# TindikSapi_V1_rev.net
KiCad netlist of a schematic drawn in EAGLE
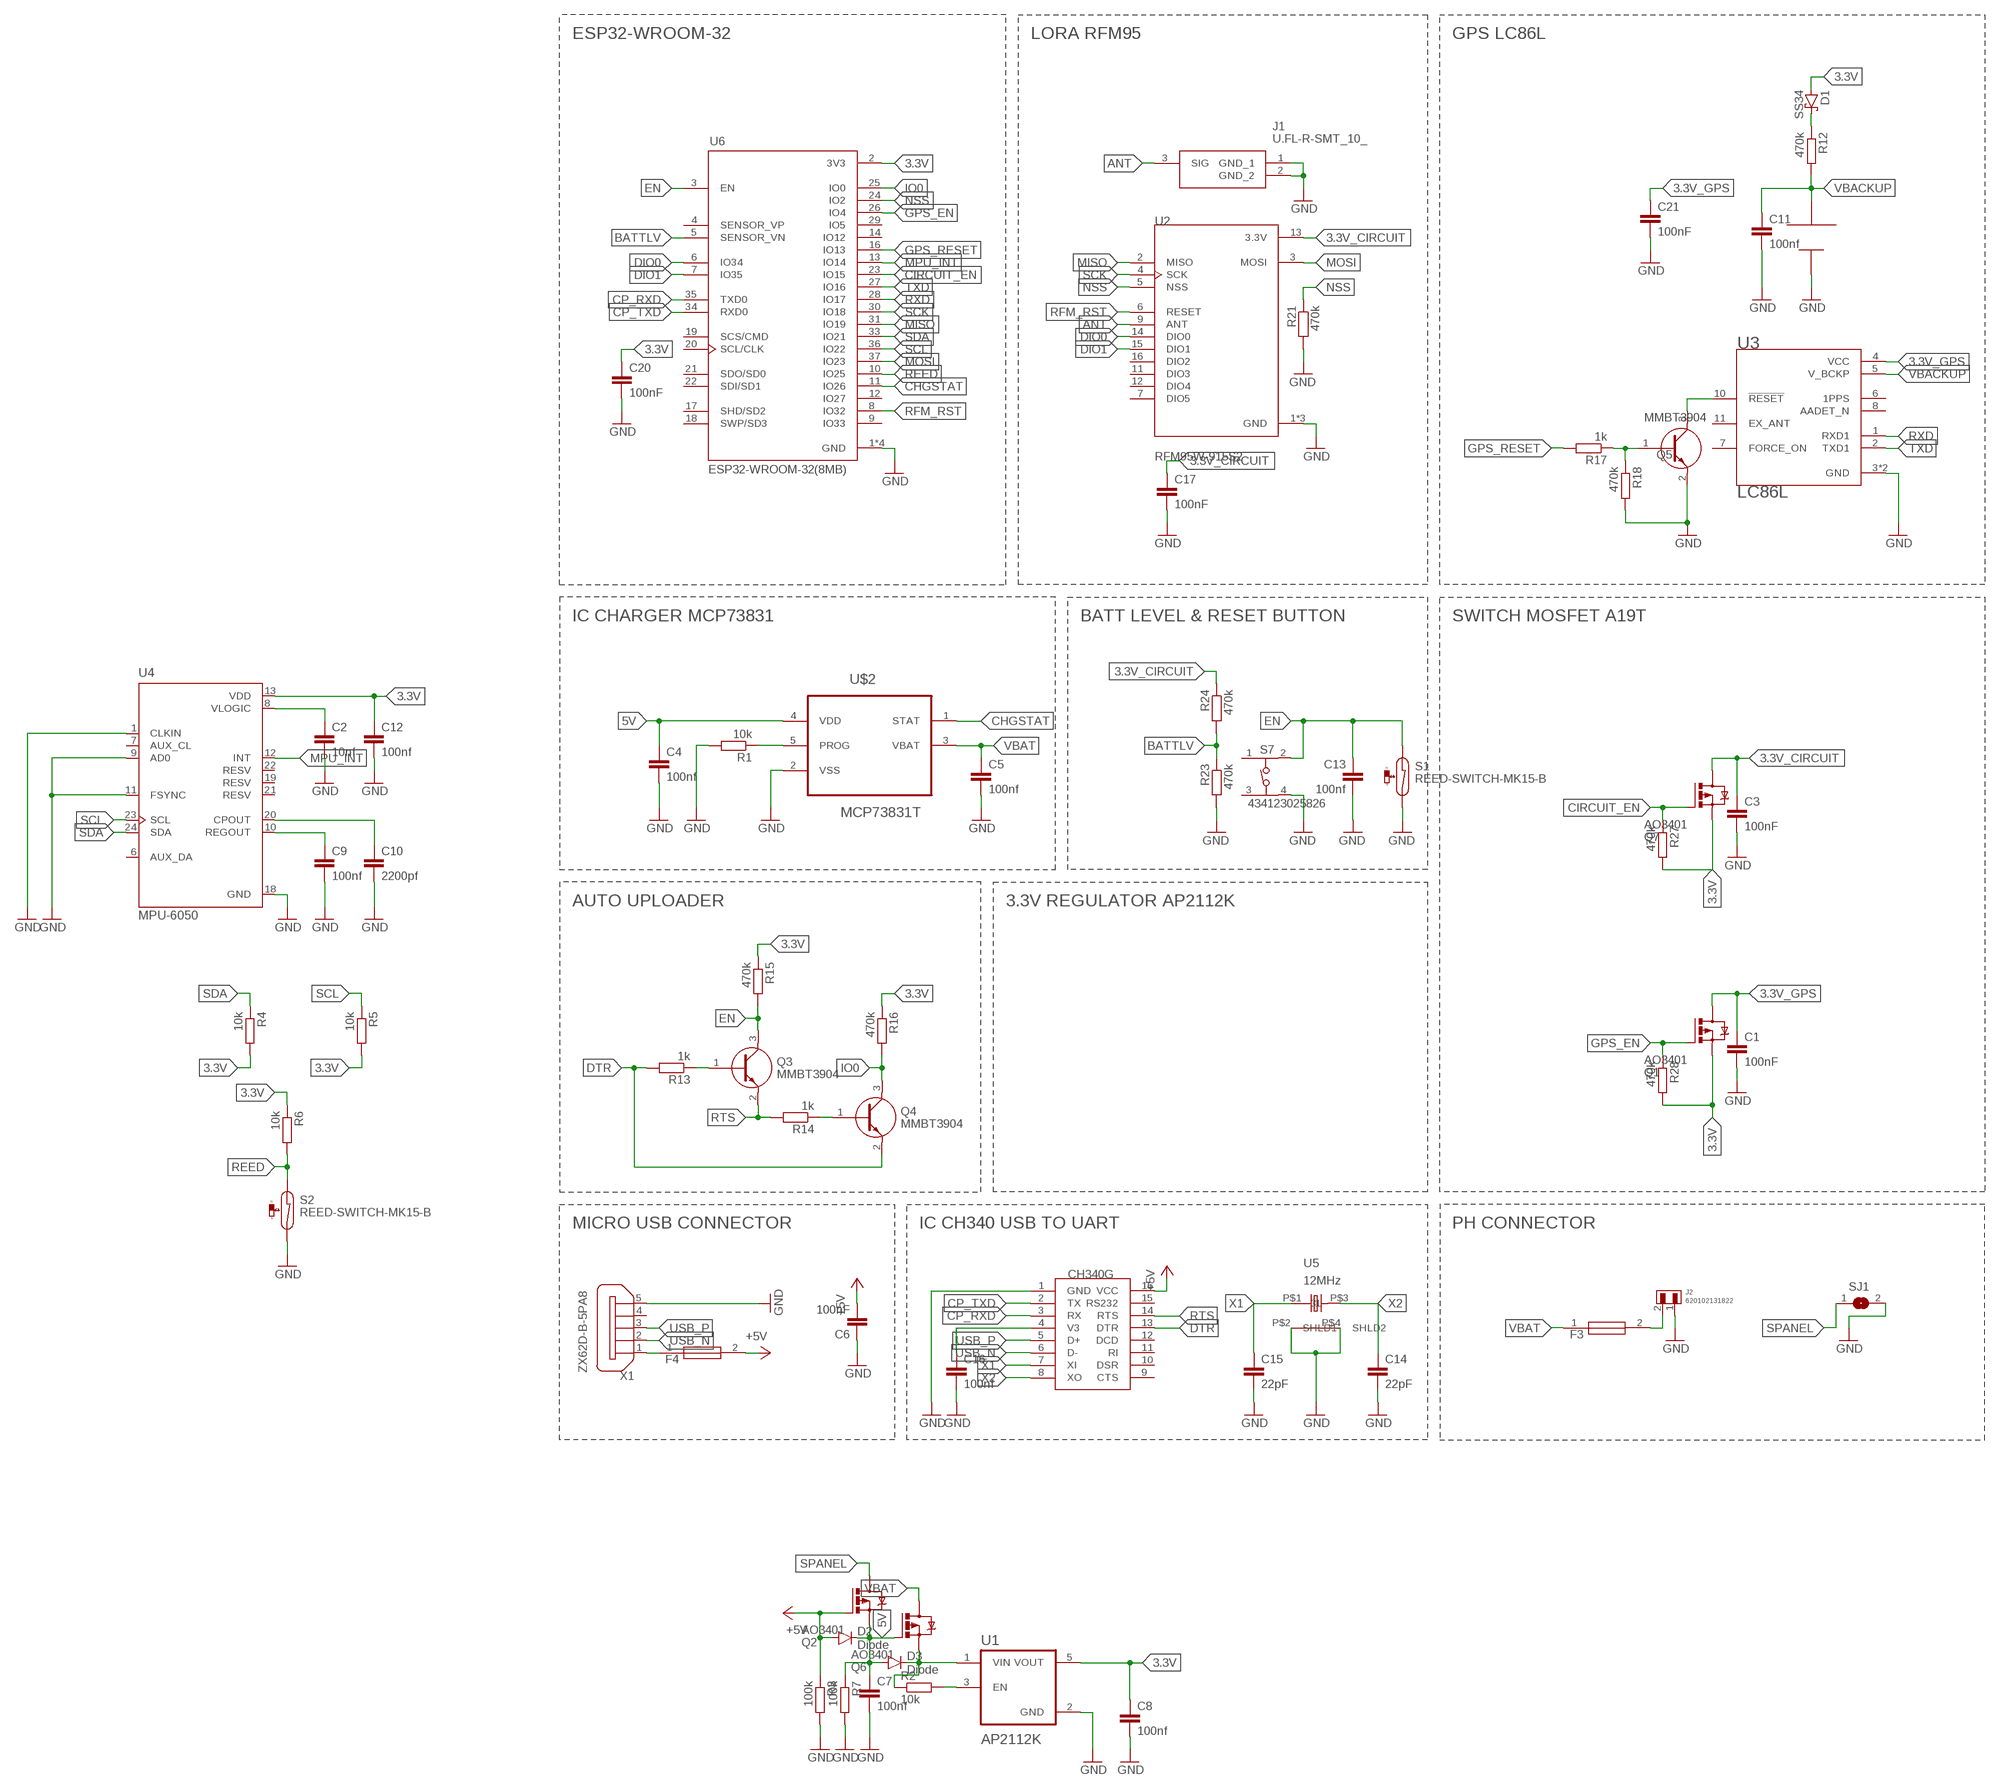
[diagram p0: schematic, sheet 1]

(export (version "E")
  (design (tool "Eeschema 10.0.6"))
  (components
    (comp (ref "C1")
      (value "100nF")
      (footprint "eagle-import:C0603")
      (libsource (lib "eagle-import") (part "C-EUC0603"))
    )
    (comp (ref "C2")
      (value "10nf")
      (footprint "eagle-import:C0603")
      (libsource (lib "eagle-import") (part "C-EUC0603"))
    )
    (comp (ref "C3")
      (value "100nF")
      (footprint "eagle-import:C0603")
      (libsource (lib "eagle-import") (part "C-EUC0603"))
    )
    (comp (ref "C4")
      (value "100nf")
      (footprint "eagle-import:C0603")
      (libsource (lib "eagle-import") (part "C-EUC0603"))
    )
    (comp (ref "C5")
      (value "100nf")
      (footprint "eagle-import:C0603")
      (libsource (lib "eagle-import") (part "C-EUC0603"))
    )
    (comp (ref "C6")
      (value "100nF")
      (footprint "eagle-import:C0603")
      (libsource (lib "eagle-import") (part "C-EUC0603"))
    )
    (comp (ref "C7")
      (value "100nf")
      (footprint "eagle-import:C0603")
      (libsource (lib "eagle-import") (part "C-EUC0603"))
    )
    (comp (ref "C8")
      (value "100nf")
      (footprint "eagle-import:C0603")
      (libsource (lib "eagle-import") (part "C-EUC0603"))
    )
    (comp (ref "C9")
      (value "100nf")
      (footprint "eagle-import:C0603")
      (libsource (lib "eagle-import") (part "C-EUC0603"))
    )
    (comp (ref "C10")
      (value "2200pf")
      (footprint "eagle-import:C0603")
      (libsource (lib "eagle-import") (part "C-EUC0603"))
    )
    (comp (ref "C11")
      (value "100nf")
      (footprint "eagle-import:C0603")
      (libsource (lib "eagle-import") (part "C-EUC0603"))
    )
    (comp (ref "C12")
      (value "100nf")
      (footprint "eagle-import:C0603")
      (libsource (lib "eagle-import") (part "C-EUC0603"))
    )
    (comp (ref "C13")
      (value "100nf")
      (footprint "eagle-import:C0603")
      (libsource (lib "eagle-import") (part "C-EUC0603"))
    )
    (comp (ref "C14")
      (value "22pF")
      (footprint "eagle-import:C0603")
      (libsource (lib "eagle-import") (part "C-EUC0603"))
    )
    (comp (ref "C15")
      (value "22pF")
      (footprint "eagle-import:C0603")
      (libsource (lib "eagle-import") (part "C-EUC0603"))
    )
    (comp (ref "C16")
      (value "100nf")
      (footprint "eagle-import:C0603")
      (libsource (lib "eagle-import") (part "C-EUC0603"))
    )
    (comp (ref "C17")
      (value "100nF")
      (footprint "eagle-import:C0603")
      (libsource (lib "eagle-import") (part "C-EUC0603"))
    )
    (comp (ref "C20")
      (value "100nF")
      (footprint "eagle-import:C0603")
      (libsource (lib "eagle-import") (part "C-EUC0603"))
    )
    (comp (ref "C21")
      (value "100nF")
      (footprint "eagle-import:C0603")
      (libsource (lib "eagle-import") (part "C-EUC0603"))
    )
    (comp (ref "D1")
      (value "SS34")
      (footprint "eagle-import:SMA")
      (fields
        (field (name "DIGIKEY_PART_NUMBER") "SS12FSCT-ND")
        (field (name "MANUFACTURER") "ON Semiconductor")
        (field (name "MPN") "SS12")
        (field (name "CREATED_BY") "PCBLayout.com")
      )
      (libsource (lib "eagle-import") (part "SS12"))
    )
    (comp (ref "D2")
      (value "Diode")
      (footprint "eagle-import:SOD123")
      (libsource (lib "eagle-import") (part "DIODE-SOD123"))
    )
    (comp (ref "D3")
      (value "Diode")
      (footprint "eagle-import:SOD123")
      (libsource (lib "eagle-import") (part "DIODE-SOD123"))
    )
    (comp (ref "F3")
      (value "FUSE 1A")
      (footprint "eagle-import:FUSC3216X100N")
      (fields
        (field (name "ARROW_PART_NUMBER") "MF-NSML260/12-2")
        (field (name "MOUSER_PART_NUMBER") "652-MF-NSML260/12-2")
      )
      (libsource (lib "eagle-import") (part "MF-NSML260_12-2"))
    )
    (comp (ref "F4")
      (value "FUSE 1A")
      (footprint "eagle-import:FUSC3216X100N")
      (fields
        (field (name "ARROW_PART_NUMBER") "MF-NSML260/12-2")
        (field (name "MOUSER_PART_NUMBER") "652-MF-NSML260/12-2")
      )
      (libsource (lib "eagle-import") (part "MF-NSML260_12-2"))
    )
    (comp (ref "J1")
      (value "U.FL-R-SMT_10_")
      (footprint "eagle-import:UFLRSMT10")
      (fields
        (field (name "ARROW_PART_NUMBER") "U.FL-R-SMT(10)")
        (field (name "MOUSER_PART_NUMBER") "798-U.FL-R-SMT10")
      )
      (libsource (lib "eagle-import") (part "U.FL-R-SMT_10_"))
    )
    (comp (ref "J2")
      (value "620102131822")
      (footprint "eagle-import:620102131822")
      (libsource (lib "eagle-import") (part "620102131822"))
    )
    (comp (ref "Q1")
      (value "AO3401")
      (footprint "eagle-import:SOT23")
      (libsource (lib "eagle-import") (part "PMOSFETSOT23_"))
    )
    (comp (ref "Q2")
      (value "AO3401")
      (footprint "eagle-import:SOT23")
      (libsource (lib "eagle-import") (part "PMOSFETSOT23_"))
    )
    (comp (ref "Q3")
      (value "MMBT3904")
      (footprint "eagle-import:SOT95P240X120-3N")
      (fields (field (name "MOUSER_PART_NUMBER") "512-MMBT3904"))
      (libsource (lib "eagle-import") (part "MMBT3904"))
    )
    (comp (ref "Q4")
      (value "MMBT3904")
      (footprint "eagle-import:SOT95P240X120-3N")
      (fields (field (name "MOUSER_PART_NUMBER") "512-MMBT3904"))
      (libsource (lib "eagle-import") (part "MMBT3904"))
    )
    (comp (ref "Q5")
      (value "MMBT3904")
      (footprint "eagle-import:SOT95P240X120-3N")
      (fields (field (name "MOUSER_PART_NUMBER") "512-MMBT3904"))
      (libsource (lib "eagle-import") (part "MMBT3904"))
    )
    (comp (ref "Q6")
      (value "AO3401")
      (footprint "eagle-import:SOT23")
      (libsource (lib "eagle-import") (part "PMOSFETSOT23_"))
    )
    (comp (ref "Q7")
      (value "AO3401")
      (footprint "eagle-import:SOT23")
      (libsource (lib "eagle-import") (part "PMOSFETSOT23_"))
    )
    (comp (ref "R1")
      (value "10k")
      (footprint "eagle-import:R0603")
      (libsource (lib "eagle-import") (part "R-EU_R0603"))
    )
    (comp (ref "R2")
      (value "10k")
      (footprint "eagle-import:R0603")
      (libsource (lib "eagle-import") (part "R-EU_R0603"))
    )
    (comp (ref "R3")
      (value "100k")
      (footprint "eagle-import:R0603")
      (libsource (lib "eagle-import") (part "R-EU_R0603"))
    )
    (comp (ref "R4")
      (value "10k")
      (footprint "eagle-import:R0603")
      (libsource (lib "eagle-import") (part "R-EU_R0603"))
    )
    (comp (ref "R5")
      (value "10k")
      (footprint "eagle-import:R0603")
      (libsource (lib "eagle-import") (part "R-EU_R0603"))
    )
    (comp (ref "R6")
      (value "10k")
      (footprint "eagle-import:R0603")
      (libsource (lib "eagle-import") (part "R-EU_R0603"))
    )
    (comp (ref "R7")
      (value "100k")
      (footprint "eagle-import:R0603")
      (libsource (lib "eagle-import") (part "R-EU_R0603"))
    )
    (comp (ref "R12")
      (value "470k")
      (footprint "eagle-import:R0603")
      (libsource (lib "eagle-import") (part "R-EU_R0603"))
    )
    (comp (ref "R13")
      (value "1k")
      (footprint "eagle-import:R0603")
      (libsource (lib "eagle-import") (part "R-EU_R0603"))
    )
    (comp (ref "R14")
      (value "1k")
      (footprint "eagle-import:R0603")
      (libsource (lib "eagle-import") (part "R-EU_R0603"))
    )
    (comp (ref "R15")
      (value "470k")
      (footprint "eagle-import:R0603")
      (libsource (lib "eagle-import") (part "R-EU_R0603"))
    )
    (comp (ref "R16")
      (value "470k")
      (footprint "eagle-import:R0603")
      (libsource (lib "eagle-import") (part "R-EU_R0603"))
    )
    (comp (ref "R17")
      (value "1k")
      (footprint "eagle-import:R0603")
      (libsource (lib "eagle-import") (part "R-EU_R0603"))
    )
    (comp (ref "R18")
      (value "470k")
      (footprint "eagle-import:R0603")
      (libsource (lib "eagle-import") (part "R-EU_R0603"))
    )
    (comp (ref "R21")
      (value "470k")
      (footprint "eagle-import:R0603")
      (libsource (lib "eagle-import") (part "R-EU_R0603"))
    )
    (comp (ref "R23")
      (value "470k")
      (footprint "eagle-import:R0603")
      (libsource (lib "eagle-import") (part "R-EU_R0603"))
    )
    (comp (ref "R24")
      (value "470k")
      (footprint "eagle-import:R0603")
      (libsource (lib "eagle-import") (part "R-EU_R0603"))
    )
    (comp (ref "R27")
      (value "470k")
      (footprint "eagle-import:R0603")
      (libsource (lib "eagle-import") (part "R-EU_R0603"))
    )
    (comp (ref "R28")
      (value "470k")
      (footprint "eagle-import:R0603")
      (libsource (lib "eagle-import") (part "R-EU_R0603"))
    )
    (comp (ref "S1")
      (value "REED-SWITCH-MK15-B")
      (footprint "eagle-import:MK15")
      (fields (field (name "MF") "MEDER") (field (name "MPN") "MK15-B-2"))
      (libsource (lib "eagle-import") (part "REED-SWITCH-MK15-B"))
    )
    (comp (ref "S2")
      (value "REED-SWITCH-MK15-B")
      (footprint "eagle-import:MK15")
      (fields (field (name "MF") "MEDER") (field (name "MPN") "MK15-B-2"))
      (libsource (lib "eagle-import") (part "REED-SWITCH-MK15-B"))
    )
    (comp (ref "S7")
      (value "434123025826")
      (footprint "eagle-import:434123025826")
      (libsource (lib "eagle-import") (part "434123025826"))
    )
    (comp (ref "SJ1")
      (value "SJW")
      (footprint "eagle-import:SJW")
      (libsource (lib "eagle-import") (part "SJW"))
    )
    (comp (ref "U$2")
      (value "MCP73831T")
      (footprint "eagle-import:SOT95P280X145-5N")
      (fields (field (name "MF") "Microchip") (field (name "MP") "MCP73831T-5ACI/OT"))
      (libsource (lib "eagle-import") (part "MCP73831T-5ACI/OT"))
    )
    (comp (ref "U$3")
      (value "MS621FE")
      (footprint "eagle-import:MS621FE")
      (libsource (lib "eagle-import") (part "MS621FE"))
    )
    (comp (ref "U$5")
      (value "CH340G")
      (footprint "eagle-import:SOIC127P600X175-16N")
      (libsource (lib "eagle-import") (part "CH340G-3D"))
    )
    (comp (ref "U1")
      (value "AP2112K")
      (footprint "eagle-import:SOT95P285X140-5N")
      (fields (field (name "MF") "Diodes Inc.") (field (name "MP") "AP2112K-3.3TRG1"))
      (libsource (lib "eagle-import") (part "AP2112K-3.3TRG1"))
    )
    (comp (ref "U2")
      (value "RFM95W-915S2")
      (footprint "eagle-import:XCVR_RFM95W-915S2")
      (fields (field (name "MF") "RF Solutions"))
      (libsource (lib "eagle-import") (part "RFM95W-915S2"))
    )
    (comp (ref "U3")
      (value "LC86L")
      (footprint "eagle-import:XCVR_L86-M33")
      (fields (field (name "MF") "Quectel") (field (name "MP") "L86-M33"))
      (libsource (lib "eagle-import") (part "L86-M33"))
    )
    (comp (ref "U4")
      (value "MPU-6050")
      (footprint "eagle-import:QFN50P400X400X95-24N")
      (fields (field (name "MF") "TDK InvenSense"))
      (libsource (lib "eagle-import") (part "MPU-6050"))
    )
    (comp (ref "U5")
      (value "12MHz")
      (footprint "eagle-import:NX32256A")
      (fields (field (name "MF") "NDK America,") (field (name "MP") "NX3225SA"))
      (libsource (lib "eagle-import") (part "NX3225SA"))
    )
    (comp (ref "U6")
      (value "ESP32-WROOM-32(8MB)")
      (footprint "eagle-import:MODULE_ESP32-WROOM-32(8MB)")
      (fields (field (name "MF") "Espressif Systems") (field (name "MP") "ESP32-WROOM-32 (8MB)"))
      (libsource (lib "eagle-import") (part "ESP32-WROOM-32(8MB)"))
    )
    (comp (ref "X1")
      (value "ZX62D-B-5PA8")
      (footprint "eagle-import:ZX62D-B-5PA8")
      (fields (field (name "MF") "Hirose"))
      (libsource (lib "eagle-import") (part "ZX62D-B-5PA8"))
    )
  )
  (nets
    (net (code "1") (name "+5V") (class "Default")
      (node (ref "C6") (pin "2") (pinfunction "2_2") (pintype "passive"))
      (node (ref "D2") (pin "A") (pinfunction "A_A") (pintype "passive"))
      (node (ref "F4") (pin "2") (pinfunction "2_2") (pintype "bidirectional"))
      (node (ref "Q2") (pin "1") (pinfunction "G_1") (pintype "passive"))
      (node (ref "R3") (pin "1") (pinfunction "1_1") (pintype "passive"))
      (node (ref "U$5") (pin "16") (pinfunction "VCC_16") (pintype "bidirectional"))
    )
    (net (code "2") (name "3.3V") (class "Default")
      (node (ref "C12") (pin "1") (pinfunction "1_1") (pintype "passive"))
      (node (ref "C20") (pin "1") (pinfunction "1_1") (pintype "passive"))
      (node (ref "C8") (pin "1") (pinfunction "1_1") (pintype "passive"))
      (node (ref "D1") (pin "A") (pinfunction "A_A") (pintype "passive"))
      (node (ref "Q1") (pin "2") (pinfunction "S_2") (pintype "passive"))
      (node (ref "Q7") (pin "2") (pinfunction "S_2") (pintype "passive"))
      (node (ref "R15") (pin "1") (pinfunction "1_1") (pintype "passive"))
      (node (ref "R16") (pin "1") (pinfunction "1_1") (pintype "passive"))
      (node (ref "R27") (pin "2") (pinfunction "2_2") (pintype "passive"))
      (node (ref "R28") (pin "2") (pinfunction "2_2") (pintype "passive"))
      (node (ref "R4") (pin "2") (pinfunction "2_2") (pintype "passive"))
      (node (ref "R5") (pin "2") (pinfunction "2_2") (pintype "passive"))
      (node (ref "R6") (pin "1") (pinfunction "1_1") (pintype "passive"))
      (node (ref "U1") (pin "5") (pinfunction "VOUT_5") (pintype "power_in"))
      (node (ref "U4") (pin "13") (pinfunction "VDD_13") (pintype "power_in"))
      (node (ref "U6") (pin "2") (pinfunction "3V3_2") (pintype "power_in"))
    )
    (net (code "3") (name "3.3V_CIRCUIT") (class "Default")
      (node (ref "C17") (pin "1") (pinfunction "1_1") (pintype "passive"))
      (node (ref "C3") (pin "1") (pinfunction "1_1") (pintype "passive"))
      (node (ref "Q7") (pin "3") (pinfunction "D_3") (pintype "passive"))
      (node (ref "R24") (pin "1") (pinfunction "1_1") (pintype "passive"))
      (node (ref "U2") (pin "13") (pinfunction "3.3V_13") (pintype "power_in"))
    )
    (net (code "4") (name "3.3V_GPS") (class "Default")
      (node (ref "C1") (pin "1") (pinfunction "1_1") (pintype "passive"))
      (node (ref "C21") (pin "1") (pinfunction "1_1") (pintype "passive"))
      (node (ref "Q1") (pin "3") (pinfunction "D_3") (pintype "passive"))
      (node (ref "U3") (pin "4") (pinfunction "VCC_4") (pintype "power_in"))
    )
    (net (code "5") (name "5V") (class "Default")
      (node (ref "C4") (pin "1") (pinfunction "1_1") (pintype "passive"))
      (node (ref "C7") (pin "1") (pinfunction "1_1") (pintype "passive"))
      (node (ref "D2") (pin "C") (pinfunction "C_C") (pintype "passive"))
      (node (ref "D3") (pin "A") (pinfunction "A_A") (pintype "passive"))
      (node (ref "Q2") (pin "2") (pinfunction "S_2") (pintype "passive"))
      (node (ref "Q6") (pin "1") (pinfunction "G_1") (pintype "passive"))
      (node (ref "R7") (pin "1") (pinfunction "1_1") (pintype "passive"))
      (node (ref "U$2") (pin "4") (pinfunction "VDD_4") (pintype "power_in"))
    )
    (net (code "6") (name "ANT") (class "Default")
      (node (ref "J1") (pin "3") (pinfunction "SIG_3") (pintype "bidirectional"))
      (node (ref "U2") (pin "9") (pinfunction "ANT_9") (pintype "bidirectional"))
    )
    (net (code "7") (name "BATTLV") (class "Default")
      (node (ref "R23") (pin "1") (pinfunction "1_1") (pintype "passive"))
      (node (ref "R24") (pin "2") (pinfunction "2_2") (pintype "passive"))
      (node (ref "U6") (pin "5") (pinfunction "SENSOR_VN_5") (pintype "input"))
    )
    (net (code "8") (name "CHGSTAT") (class "Default")
      (node (ref "U$2") (pin "1") (pinfunction "STAT_1") (pintype "output"))
      (node (ref "U6") (pin "11") (pinfunction "IO26_11") (pintype "bidirectional"))
    )
    (net (code "9") (name "CIRCUIT_EN") (class "Default")
      (node (ref "Q7") (pin "1") (pinfunction "G_1") (pintype "passive"))
      (node (ref "R27") (pin "1") (pinfunction "1_1") (pintype "passive"))
      (node (ref "U6") (pin "23") (pinfunction "IO15_23") (pintype "bidirectional"))
    )
    (net (code "10") (name "CP_RXD") (class "Default")
      (node (ref "U$5") (pin "3") (pinfunction "RX_3") (pintype "bidirectional"))
      (node (ref "U6") (pin "35") (pinfunction "TXD0_35") (pintype "bidirectional"))
    )
    (net (code "11") (name "CP_TXD") (class "Default")
      (node (ref "U$5") (pin "2") (pinfunction "TX_2") (pintype "bidirectional"))
      (node (ref "U6") (pin "34") (pinfunction "RXD0_34") (pintype "bidirectional"))
    )
    (net (code "12") (name "DIO0") (class "Default")
      (node (ref "U2") (pin "14") (pinfunction "DIO0_14") (pintype "bidirectional"))
      (node (ref "U6") (pin "6") (pinfunction "IO34_6") (pintype "input"))
    )
    (net (code "13") (name "DIO1") (class "Default")
      (node (ref "U2") (pin "15") (pinfunction "DIO1_15") (pintype "bidirectional"))
      (node (ref "U6") (pin "7") (pinfunction "IO35_7") (pintype "input"))
    )
    (net (code "14") (name "DTR") (class "Default")
      (node (ref "Q4") (pin "2") (pinfunction "E_2") (pintype "bidirectional"))
      (node (ref "R13") (pin "2") (pinfunction "2_2") (pintype "passive"))
      (node (ref "U$5") (pin "13") (pinfunction "DTR_13") (pintype "bidirectional"))
    )
    (net (code "15") (name "EN") (class "Default")
      (node (ref "C13") (pin "1") (pinfunction "1_1") (pintype "passive"))
      (node (ref "Q3") (pin "3") (pinfunction "C_3") (pintype "bidirectional"))
      (node (ref "R15") (pin "2") (pinfunction "2_2") (pintype "passive"))
      (node (ref "S1") (pin "1") (pinfunction "1_1") (pintype "passive"))
      (node (ref "S7") (pin "2") (pinfunction "2_2") (pintype "passive"))
      (node (ref "U6") (pin "3") (pinfunction "EN_3") (pintype "input"))
    )
    (net (code "16") (name "GND") (class "Default")
      (node (ref "C1") (pin "2") (pinfunction "2_2") (pintype "passive"))
      (node (ref "C10") (pin "2") (pinfunction "2_2") (pintype "passive"))
      (node (ref "C11") (pin "2") (pinfunction "2_2") (pintype "passive"))
      (node (ref "C12") (pin "2") (pinfunction "2_2") (pintype "passive"))
      (node (ref "C13") (pin "2") (pinfunction "2_2") (pintype "passive"))
      (node (ref "C14") (pin "2") (pinfunction "2_2") (pintype "passive"))
      (node (ref "C15") (pin "2") (pinfunction "2_2") (pintype "passive"))
      (node (ref "C16") (pin "2") (pinfunction "2_2") (pintype "passive"))
      (node (ref "C17") (pin "2") (pinfunction "2_2") (pintype "passive"))
      (node (ref "C2") (pin "2") (pinfunction "2_2") (pintype "passive"))
      (node (ref "C20") (pin "2") (pinfunction "2_2") (pintype "passive"))
      (node (ref "C21") (pin "2") (pinfunction "2_2") (pintype "passive"))
      (node (ref "C3") (pin "2") (pinfunction "2_2") (pintype "passive"))
      (node (ref "C4") (pin "2") (pinfunction "2_2") (pintype "passive"))
      (node (ref "C5") (pin "2") (pinfunction "2_2") (pintype "passive"))
      (node (ref "C6") (pin "1") (pinfunction "1_1") (pintype "passive"))
      (node (ref "C7") (pin "2") (pinfunction "2_2") (pintype "passive"))
      (node (ref "C8") (pin "2") (pinfunction "2_2") (pintype "passive"))
      (node (ref "C9") (pin "2") (pinfunction "2_2") (pintype "passive"))
      (node (ref "J1") (pin "1") (pinfunction "GND_1_1") (pintype "bidirectional"))
      (node (ref "J1") (pin "2") (pinfunction "GND_2_2") (pintype "bidirectional"))
      (node (ref "J2") (pin "1") (pinfunction "1_1") (pintype "passive"))
      (node (ref "Q5") (pin "2") (pinfunction "E_2") (pintype "bidirectional"))
      (node (ref "R1") (pin "2") (pinfunction "2_2") (pintype "passive"))
      (node (ref "R18") (pin "2") (pinfunction "2_2") (pintype "passive"))
      (node (ref "R21") (pin "2") (pinfunction "2_2") (pintype "passive"))
      (node (ref "R23") (pin "2") (pinfunction "2_2") (pintype "passive"))
      (node (ref "R3") (pin "2") (pinfunction "2_2") (pintype "passive"))
      (node (ref "R7") (pin "2") (pinfunction "2_2") (pintype "passive"))
      (node (ref "S1") (pin "2") (pinfunction "2_2") (pintype "passive"))
      (node (ref "S2") (pin "2") (pinfunction "2_2") (pintype "passive"))
      (node (ref "S7") (pin "4") (pinfunction "4_4") (pintype "passive"))
      (node (ref "SJ1") (pin "2") (pinfunction "2_2") (pintype "passive"))
      (node (ref "U$2") (pin "2") (pinfunction "VSS_2") (pintype "power_in"))
      (node (ref "U$3") (pin "V-") (pinfunction "V-_V-") (pintype "bidirectional"))
      (node (ref "U$5") (pin "1") (pinfunction "GND_1") (pintype "bidirectional"))
      (node (ref "U1") (pin "2") (pinfunction "GND_2") (pintype "power_in"))
      (node (ref "U2") (pin "1") (pinfunction "GND_1") (pintype "power_in"))
      (node (ref "U2") (pin "10") (pinfunction "GND_10") (pintype "power_in"))
      (node (ref "U2") (pin "8") (pinfunction "GND_8") (pintype "power_in"))
      (node (ref "U3") (pin "12") (pinfunction "GND_12") (pintype "passive"))
      (node (ref "U3") (pin "3") (pinfunction "GND_3") (pintype "passive"))
      (node (ref "U4") (pin "1") (pinfunction "CLKIN_1") (pintype "input"))
      (node (ref "U4") (pin "11") (pinfunction "FSYNC_11") (pintype "input"))
      (node (ref "U4") (pin "18") (pinfunction "GND_18") (pintype "power_in"))
      (node (ref "U4") (pin "9") (pinfunction "AD0_9") (pintype "input"))
      (node (ref "U5") (pin "P$2") (pinfunction "SHLD1_P$2") (pintype "passive"))
      (node (ref "U5") (pin "P$4") (pinfunction "SHLD2_P$4") (pintype "passive"))
      (node (ref "U6") (pin "1") (pinfunction "GND_1") (pintype "power_in"))
      (node (ref "U6") (pin "15") (pinfunction "GND_15") (pintype "power_in"))
      (node (ref "U6") (pin "38") (pinfunction "GND_38") (pintype "power_in"))
      (node (ref "U6") (pin "39") (pinfunction "GND_39") (pintype "power_in"))
      (node (ref "X1") (pin "5") (pinfunction "5_5") (pintype "passive"))
    )
    (net (code "17") (name "GPS_EN") (class "Default")
      (node (ref "Q1") (pin "1") (pinfunction "G_1") (pintype "passive"))
      (node (ref "R28") (pin "1") (pinfunction "1_1") (pintype "passive"))
      (node (ref "U6") (pin "26") (pinfunction "IO4_26") (pintype "bidirectional"))
    )
    (net (code "18") (name "GPS_RESET") (class "Default")
      (node (ref "R17") (pin "2") (pinfunction "2_2") (pintype "passive"))
      (node (ref "U6") (pin "16") (pinfunction "IO13_16") (pintype "bidirectional"))
    )
    (net (code "19") (name "IO0") (class "Default")
      (node (ref "Q4") (pin "3") (pinfunction "C_3") (pintype "bidirectional"))
      (node (ref "R16") (pin "2") (pinfunction "2_2") (pintype "passive"))
      (node (ref "U6") (pin "25") (pinfunction "IO0_25") (pintype "bidirectional"))
    )
    (net (code "20") (name "MISO") (class "Default")
      (node (ref "U2") (pin "2") (pinfunction "MISO_2") (pintype "input"))
      (node (ref "U6") (pin "31") (pinfunction "IO19_31") (pintype "bidirectional"))
    )
    (net (code "21") (name "MOSI") (class "Default")
      (node (ref "U2") (pin "3") (pinfunction "MOSI_3") (pintype "output"))
      (node (ref "U6") (pin "37") (pinfunction "IO23_37") (pintype "bidirectional"))
    )
    (net (code "22") (name "MPU_INT") (class "Default")
      (node (ref "U4") (pin "12") (pinfunction "INT_12") (pintype "output"))
      (node (ref "U6") (pin "13") (pinfunction "IO14_13") (pintype "bidirectional"))
    )
    (net (code "23") (name "NSS") (class "Default")
      (node (ref "R21") (pin "1") (pinfunction "1_1") (pintype "passive"))
      (node (ref "U2") (pin "5") (pinfunction "NSS_5") (pintype "input"))
      (node (ref "U6") (pin "24") (pinfunction "IO2_24") (pintype "bidirectional"))
    )
    (net (code "24") (name "Net-(D1-PadC)") (class "Default")
      (node (ref "D1") (pin "C") (pinfunction "C_C") (pintype "passive"))
      (node (ref "R12") (pin "1") (pinfunction "1_1") (pintype "passive"))
    )
    (net (code "25") (name "Net-(F3-Pad2)") (class "Default")
      (node (ref "F3") (pin "2") (pinfunction "2_2") (pintype "bidirectional"))
      (node (ref "J2") (pin "2") (pinfunction "2_2") (pintype "passive"))
    )
    (net (code "26") (name "Net-(F4-Pad1)") (class "Default")
      (node (ref "F4") (pin "1") (pinfunction "1_1") (pintype "bidirectional"))
      (node (ref "X1") (pin "1") (pinfunction "1_1") (pintype "passive"))
    )
    (net (code "27") (name "Net-(Q3-B)") (class "Default")
      (node (ref "Q3") (pin "1") (pinfunction "B_1") (pintype "bidirectional"))
      (node (ref "R13") (pin "1") (pinfunction "1_1") (pintype "passive"))
    )
    (net (code "28") (name "Net-(Q4-B)") (class "Default")
      (node (ref "Q4") (pin "1") (pinfunction "B_1") (pintype "bidirectional"))
      (node (ref "R14") (pin "1") (pinfunction "1_1") (pintype "passive"))
    )
    (net (code "29") (name "Net-(Q5-B)") (class "Default")
      (node (ref "Q5") (pin "1") (pinfunction "B_1") (pintype "bidirectional"))
      (node (ref "R17") (pin "1") (pinfunction "1_1") (pintype "passive"))
      (node (ref "R18") (pin "1") (pinfunction "1_1") (pintype "passive"))
    )
    (net (code "30") (name "Net-(Q5-C)") (class "Default")
      (node (ref "Q5") (pin "3") (pinfunction "C_3") (pintype "bidirectional"))
      (node (ref "U3") (pin "10") (pinfunction "~{RESET}_10") (pintype "input"))
    )
    (net (code "31") (name "Net-(Q6-S)") (class "Default")
      (node (ref "D3") (pin "C") (pinfunction "C_C") (pintype "passive"))
      (node (ref "Q6") (pin "2") (pinfunction "S_2") (pintype "passive"))
      (node (ref "R2") (pin "1") (pinfunction "1_1") (pintype "passive"))
      (node (ref "U1") (pin "1") (pinfunction "VIN_1") (pintype "power_in"))
    )
    (net (code "32") (name "Net-(U$2-PROG)") (class "Default")
      (node (ref "R1") (pin "1") (pinfunction "1_1") (pintype "passive"))
      (node (ref "U$2") (pin "5") (pinfunction "PROG_5") (pintype "input"))
    )
    (net (code "33") (name "Net-(U$5-V3)") (class "Default")
      (node (ref "C16") (pin "1") (pinfunction "1_1") (pintype "passive"))
      (node (ref "U$5") (pin "4") (pinfunction "V3_4") (pintype "bidirectional"))
    )
    (net (code "34") (name "Net-(U1-EN)") (class "Default")
      (node (ref "R2") (pin "2") (pinfunction "2_2") (pintype "passive"))
      (node (ref "U1") (pin "3") (pinfunction "EN_3") (pintype "input"))
    )
    (net (code "35") (name "Net-(U4-CPOUT)") (class "Default")
      (node (ref "C10") (pin "1") (pinfunction "1_1") (pintype "passive"))
      (node (ref "U4") (pin "20") (pinfunction "CPOUT_20") (pintype "passive"))
    )
    (net (code "36") (name "Net-(U4-REGOUT)") (class "Default")
      (node (ref "C9") (pin "1") (pinfunction "1_1") (pintype "passive"))
      (node (ref "U4") (pin "10") (pinfunction "REGOUT_10") (pintype "passive"))
    )
    (net (code "37") (name "Net-(U4-VLOGIC)") (class "Default")
      (node (ref "C2") (pin "1") (pinfunction "1_1") (pintype "passive"))
      (node (ref "U4") (pin "8") (pinfunction "VLOGIC_8") (pintype "power_in"))
    )
    (net (code "38") (name "REED") (class "Default")
      (node (ref "R6") (pin "2") (pinfunction "2_2") (pintype "passive"))
      (node (ref "S2") (pin "1") (pinfunction "1_1") (pintype "passive"))
      (node (ref "U6") (pin "10") (pinfunction "IO25_10") (pintype "bidirectional"))
    )
    (net (code "39") (name "RFM_RST") (class "Default")
      (node (ref "U2") (pin "6") (pinfunction "RESET_6") (pintype "bidirectional"))
      (node (ref "U6") (pin "8") (pinfunction "IO32_8") (pintype "bidirectional"))
    )
    (net (code "40") (name "RTS") (class "Default")
      (node (ref "Q3") (pin "2") (pinfunction "E_2") (pintype "bidirectional"))
      (node (ref "R14") (pin "2") (pinfunction "2_2") (pintype "passive"))
      (node (ref "U$5") (pin "14") (pinfunction "RTS_14") (pintype "bidirectional"))
    )
    (net (code "41") (name "RXD") (class "Default")
      (node (ref "U3") (pin "1") (pinfunction "RXD1_1") (pintype "input"))
      (node (ref "U6") (pin "28") (pinfunction "IO17_28") (pintype "bidirectional"))
    )
    (net (code "42") (name "SCK") (class "Default")
      (node (ref "U2") (pin "4") (pinfunction "SCK_4") (pintype "input"))
      (node (ref "U6") (pin "30") (pinfunction "IO18_30") (pintype "bidirectional"))
    )
    (net (code "43") (name "SCL") (class "Default")
      (node (ref "R5") (pin "1") (pinfunction "1_1") (pintype "passive"))
      (node (ref "U4") (pin "23") (pinfunction "SCL_23") (pintype "input"))
      (node (ref "U6") (pin "36") (pinfunction "IO22_36") (pintype "bidirectional"))
    )
    (net (code "44") (name "SDA") (class "Default")
      (node (ref "R4") (pin "1") (pinfunction "1_1") (pintype "passive"))
      (node (ref "U4") (pin "24") (pinfunction "SDA_24") (pintype "bidirectional"))
      (node (ref "U6") (pin "33") (pinfunction "IO21_33") (pintype "bidirectional"))
    )
    (net (code "45") (name "SPANEL") (class "Default")
      (node (ref "Q2") (pin "3") (pinfunction "D_3") (pintype "passive"))
      (node (ref "SJ1") (pin "1") (pinfunction "1_1") (pintype "passive"))
    )
    (net (code "46") (name "TXD") (class "Default")
      (node (ref "U3") (pin "2") (pinfunction "TXD1_2") (pintype "output"))
      (node (ref "U6") (pin "27") (pinfunction "IO16_27") (pintype "bidirectional"))
    )
    (net (code "47") (name "USB_N") (class "Default")
      (node (ref "U$5") (pin "6") (pinfunction "D-_6") (pintype "bidirectional"))
      (node (ref "X1") (pin "2") (pinfunction "2_2") (pintype "passive"))
    )
    (net (code "48") (name "USB_P") (class "Default")
      (node (ref "U$5") (pin "5") (pinfunction "D+_5") (pintype "bidirectional"))
      (node (ref "X1") (pin "3") (pinfunction "3_3") (pintype "passive"))
    )
    (net (code "49") (name "VBACKUP") (class "Default")
      (node (ref "C11") (pin "1") (pinfunction "1_1") (pintype "passive"))
      (node (ref "R12") (pin "2") (pinfunction "2_2") (pintype "passive"))
      (node (ref "U$3") (pin "V+") (pinfunction "V+_V+") (pintype "bidirectional"))
      (node (ref "U3") (pin "5") (pinfunction "V_BCKP_5") (pintype "power_in"))
    )
    (net (code "50") (name "VBAT") (class "Default")
      (node (ref "C5") (pin "1") (pinfunction "1_1") (pintype "passive"))
      (node (ref "F3") (pin "1") (pinfunction "1_1") (pintype "bidirectional"))
      (node (ref "Q6") (pin "3") (pinfunction "D_3") (pintype "passive"))
      (node (ref "U$2") (pin "3") (pinfunction "VBAT_3") (pintype "output"))
    )
    (net (code "51") (name "X1") (class "Default")
      (node (ref "C15") (pin "1") (pinfunction "1_1") (pintype "passive"))
      (node (ref "U$5") (pin "7") (pinfunction "XI_7") (pintype "bidirectional"))
      (node (ref "U5") (pin "P$1") (pinfunction "1_P$1") (pintype "passive"))
    )
    (net (code "52") (name "X2") (class "Default")
      (node (ref "C14") (pin "1") (pinfunction "1_1") (pintype "passive"))
      (node (ref "U$5") (pin "8") (pinfunction "XO_8") (pintype "bidirectional"))
      (node (ref "U5") (pin "P$3") (pinfunction "3_P$3") (pintype "passive"))
    )
    (net (code "53") (name "unconnected-(S7-Pad1)") (class "Default")
      (node (ref "S7") (pin "1") (pinfunction "1_1") (pintype "passive"))
    )
    (net (code "54") (name "unconnected-(S7-Pad3)") (class "Default")
      (node (ref "S7") (pin "3") (pinfunction "3_3") (pintype "passive"))
    )
    (net (code "55") (name "unconnected-(U$5-CTS-Pad9)") (class "Default")
      (node (ref "U$5") (pin "9") (pinfunction "CTS_9") (pintype "bidirectional"))
    )
    (net (code "56") (name "unconnected-(U$5-DCD-Pad12)") (class "Default")
      (node (ref "U$5") (pin "12") (pinfunction "DCD_12") (pintype "bidirectional"))
    )
    (net (code "57") (name "unconnected-(U$5-DSR-Pad10)") (class "Default")
      (node (ref "U$5") (pin "10") (pinfunction "DSR_10") (pintype "bidirectional"))
    )
    (net (code "58") (name "unconnected-(U$5-RI-Pad11)") (class "Default")
      (node (ref "U$5") (pin "11") (pinfunction "RI_11") (pintype "bidirectional"))
    )
    (net (code "59") (name "unconnected-(U$5-RS232-Pad15)") (class "Default")
      (node (ref "U$5") (pin "15") (pinfunction "RS232_15") (pintype "bidirectional"))
    )
    (net (code "60") (name "unconnected-(U2-DIO2-Pad16)") (class "Default")
      (node (ref "U2") (pin "16") (pinfunction "DIO2_16") (pintype "bidirectional"))
    )
    (net (code "61") (name "unconnected-(U2-DIO3-Pad11)") (class "Default")
      (node (ref "U2") (pin "11") (pinfunction "DIO3_11") (pintype "bidirectional"))
    )
    (net (code "62") (name "unconnected-(U2-DIO4-Pad12)") (class "Default")
      (node (ref "U2") (pin "12") (pinfunction "DIO4_12") (pintype "bidirectional"))
    )
    (net (code "63") (name "unconnected-(U2-DIO5-Pad7)") (class "Default")
      (node (ref "U2") (pin "7") (pinfunction "DIO5_7") (pintype "bidirectional"))
    )
    (net (code "64") (name "unconnected-(U3-1PPS-Pad6)") (class "Default")
      (node (ref "U3") (pin "6") (pinfunction "1PPS_6") (pintype "output"))
    )
    (net (code "65") (name "unconnected-(U3-AADET_N-Pad8)") (class "Default")
      (node (ref "U3") (pin "8") (pinfunction "AADET_N_8") (pintype "output"))
    )
    (net (code "66") (name "unconnected-(U3-EX_ANT-Pad11)") (class "Default")
      (node (ref "U3") (pin "11") (pinfunction "EX_ANT_11") (pintype "input"))
    )
    (net (code "67") (name "unconnected-(U3-FORCE_ON-Pad7)") (class "Default")
      (node (ref "U3") (pin "7") (pinfunction "FORCE_ON_7") (pintype "input"))
    )
    (net (code "68") (name "unconnected-(U4-AUX_CL-Pad7)") (class "Default")
      (node (ref "U4") (pin "7") (pinfunction "AUX_CL_7") (pintype "input"))
    )
    (net (code "69") (name "unconnected-(U4-AUX_DA-Pad6)") (class "Default")
      (node (ref "U4") (pin "6") (pinfunction "AUX_DA_6") (pintype "bidirectional"))
    )
    (net (code "70") (name "unconnected-(U4-RESV-Pad19)") (class "Default")
      (node (ref "U4") (pin "19") (pinfunction "RESV_19") (pintype "passive"))
    )
    (net (code "71") (name "unconnected-(U4-RESV-Pad21)") (class "Default")
      (node (ref "U4") (pin "21") (pinfunction "RESV_21") (pintype "passive"))
    )
    (net (code "72") (name "unconnected-(U4-RESV-Pad22)") (class "Default")
      (node (ref "U4") (pin "22") (pinfunction "RESV_22") (pintype "passive"))
    )
    (net (code "73") (name "unconnected-(U6-IO5-Pad29)") (class "Default")
      (node (ref "U6") (pin "29") (pinfunction "IO5_29") (pintype "bidirectional"))
    )
    (net (code "74") (name "unconnected-(U6-IO12-Pad14)") (class "Default")
      (node (ref "U6") (pin "14") (pinfunction "IO12_14") (pintype "bidirectional"))
    )
    (net (code "75") (name "unconnected-(U6-IO27-Pad12)") (class "Default")
      (node (ref "U6") (pin "12") (pinfunction "IO27_12") (pintype "bidirectional"))
    )
    (net (code "76") (name "unconnected-(U6-IO33-Pad9)") (class "Default")
      (node (ref "U6") (pin "9") (pinfunction "IO33_9") (pintype "bidirectional"))
    )
    (net (code "77") (name "unconnected-(U6-SCL{slash}CLK-Pad20)") (class "Default")
      (node (ref "U6") (pin "20") (pinfunction "SCL/CLK_20") (pintype "bidirectional"))
    )
    (net (code "78") (name "unconnected-(U6-SCS{slash}CMD-Pad19)") (class "Default")
      (node (ref "U6") (pin "19") (pinfunction "SCS/CMD_19") (pintype "bidirectional"))
    )
    (net (code "79") (name "unconnected-(U6-SDI{slash}SD1-Pad22)") (class "Default")
      (node (ref "U6") (pin "22") (pinfunction "SDI/SD1_22") (pintype "bidirectional"))
    )
    (net (code "80") (name "unconnected-(U6-SDO{slash}SD0-Pad21)") (class "Default")
      (node (ref "U6") (pin "21") (pinfunction "SDO/SD0_21") (pintype "bidirectional"))
    )
    (net (code "81") (name "unconnected-(U6-SENSOR_VP-Pad4)") (class "Default")
      (node (ref "U6") (pin "4") (pinfunction "SENSOR_VP_4") (pintype "input"))
    )
    (net (code "82") (name "unconnected-(U6-SHD{slash}SD2-Pad17)") (class "Default")
      (node (ref "U6") (pin "17") (pinfunction "SHD/SD2_17") (pintype "bidirectional"))
    )
    (net (code "83") (name "unconnected-(U6-SWP{slash}SD3-Pad18)") (class "Default")
      (node (ref "U6") (pin "18") (pinfunction "SWP/SD3_18") (pintype "bidirectional"))
    )
    (net (code "84") (name "unconnected-(X1-Pad4)") (class "Default")
      (node (ref "X1") (pin "4") (pinfunction "4_4") (pintype "passive"))
    )
  )
)
